# AS3364_bus_mixer_v2_0.net
KiCad netlist of a schematic drawn in EAGLE
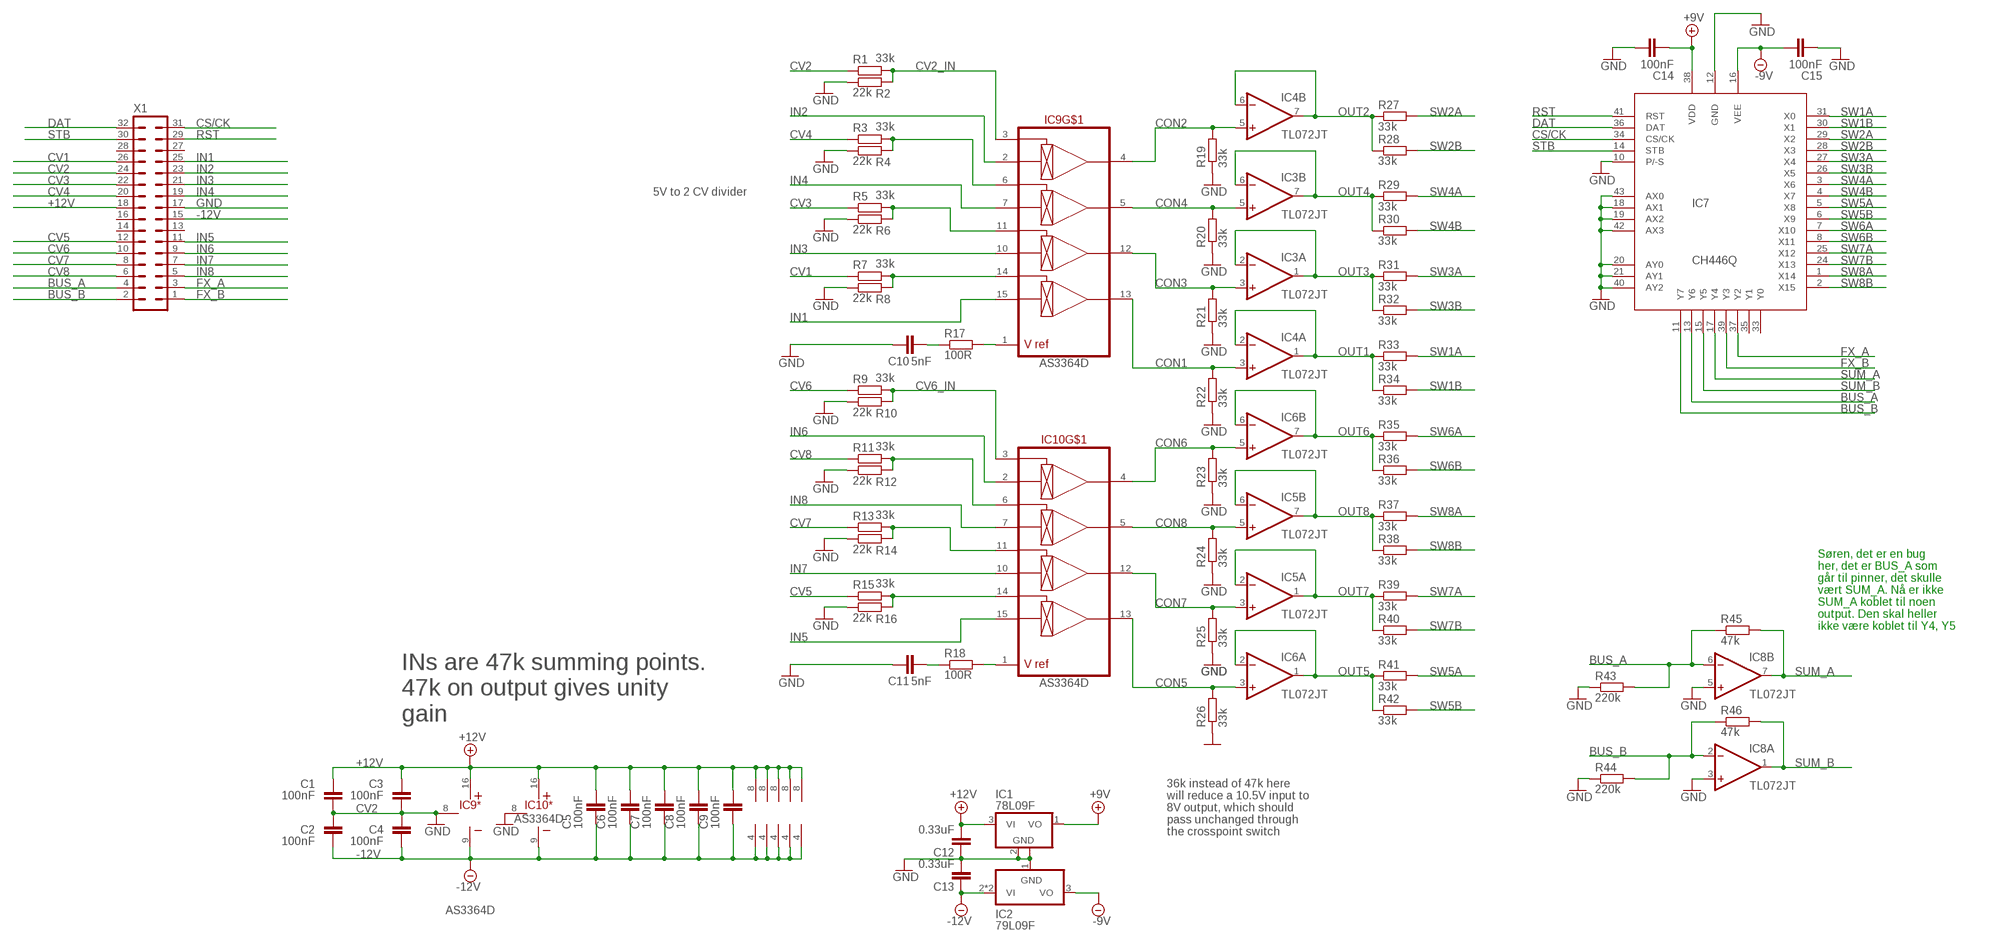
[diagram p0: schematic, sheet 1]

(export (version "E")
  (design (tool "Eeschema 10.0.6"))
  (components
    (comp (ref "C1")
      (value "100nF")
      (footprint "eagle-import:C0402")
      (libsource (lib "eagle-import") (part "C-EUC0402"))
    )
    (comp (ref "C2")
      (value "100nF")
      (footprint "eagle-import:C0402")
      (libsource (lib "eagle-import") (part "C-EUC0402"))
    )
    (comp (ref "C3")
      (value "100nF")
      (footprint "eagle-import:C0402")
      (libsource (lib "eagle-import") (part "C-EUC0402"))
    )
    (comp (ref "C4")
      (value "100nF")
      (footprint "eagle-import:C0402")
      (libsource (lib "eagle-import") (part "C-EUC0402"))
    )
    (comp (ref "C5")
      (value "100nF")
      (footprint "eagle-import:C0402")
      (libsource (lib "eagle-import") (part "C-EUC0402"))
    )
    (comp (ref "C6")
      (value "100nF")
      (footprint "eagle-import:C0402")
      (libsource (lib "eagle-import") (part "C-EUC0402"))
    )
    (comp (ref "C7")
      (value "100nF")
      (footprint "eagle-import:C0402")
      (libsource (lib "eagle-import") (part "C-EUC0402"))
    )
    (comp (ref "C8")
      (value "100nF")
      (footprint "eagle-import:C0402")
      (libsource (lib "eagle-import") (part "C-EUC0402"))
    )
    (comp (ref "C9")
      (value "100nF")
      (footprint "eagle-import:C0402")
      (libsource (lib "eagle-import") (part "C-EUC0402"))
    )
    (comp (ref "C10")
      (value "5nF")
      (footprint "eagle-import:C0402")
      (libsource (lib "eagle-import") (part "C-EUC0402"))
    )
    (comp (ref "C11")
      (value "5nF")
      (footprint "eagle-import:C0402")
      (libsource (lib "eagle-import") (part "C-EUC0402"))
    )
    (comp (ref "C12")
      (value "0.33uF")
      (footprint "eagle-import:C0603")
      (libsource (lib "eagle-import") (part "resistor_C-EUC0603"))
    )
    (comp (ref "C13")
      (value "0.33uF")
      (footprint "eagle-import:C0603")
      (libsource (lib "eagle-import") (part "resistor_C-EUC0603"))
    )
    (comp (ref "C14")
      (value "100nF")
      (footprint "eagle-import:C0402")
      (libsource (lib "eagle-import") (part "C-EUC0402"))
    )
    (comp (ref "C15")
      (value "100nF")
      (footprint "eagle-import:C0402")
      (libsource (lib "eagle-import") (part "C-EUC0402"))
    )
    (comp (ref "IC1")
      (value "78L09F")
      (footprint "eagle-import:SOT89")
      (libsource (lib "eagle-import") (part "78LF09"))
    )
    (comp (ref "IC2")
      (value "79L09F")
      (footprint "eagle-import:SOT89")
      (libsource (lib "eagle-import") (part "79LF09"))
    )
    (comp (ref "IC3")
      (value "TL072JT")
      (footprint "eagle-import:TSSOP8J")
      (libsource (lib "eagle-import") (part "TL072JT"))
    )
    (comp (ref "IC4")
      (value "TL072JT")
      (footprint "eagle-import:TSSOP8J")
      (libsource (lib "eagle-import") (part "TL072JT"))
    )
    (comp (ref "IC5")
      (value "TL072JT")
      (footprint "eagle-import:TSSOP8J")
      (libsource (lib "eagle-import") (part "TL072JT"))
    )
    (comp (ref "IC6")
      (value "TL072JT")
      (footprint "eagle-import:TSSOP8J")
      (libsource (lib "eagle-import") (part "TL072JT"))
    )
    (comp (ref "IC7")
      (value "CH446Q")
      (footprint "eagle-import:LQFP-44-J")
      (libsource (lib "eagle-import") (part "CH446Q"))
    )
    (comp (ref "IC8")
      (value "TL072JT")
      (footprint "eagle-import:TSSOP8J")
      (libsource (lib "eagle-import") (part "TL072JT"))
    )
    (comp (ref "IC9")
      (value "AS3364D")
      (footprint "eagle-import:DIL16J")
      (libsource (lib "eagle-import") (part "AS3364D"))
    )
    (comp (ref "IC10")
      (value "AS3364D")
      (footprint "eagle-import:DIL16J")
      (libsource (lib "eagle-import") (part "AS3364D"))
    )
    (comp (ref "R1")
      (value "33k")
      (footprint "eagle-import:R0402")
      (libsource (lib "eagle-import") (part "R-EU_R0402"))
    )
    (comp (ref "R2")
      (value "22k")
      (footprint "eagle-import:R0402")
      (libsource (lib "eagle-import") (part "R-EU_R0402"))
    )
    (comp (ref "R3")
      (value "33k")
      (footprint "eagle-import:R0402")
      (libsource (lib "eagle-import") (part "R-EU_R0402"))
    )
    (comp (ref "R4")
      (value "22k")
      (footprint "eagle-import:R0402")
      (libsource (lib "eagle-import") (part "R-EU_R0402"))
    )
    (comp (ref "R5")
      (value "33k")
      (footprint "eagle-import:R0402")
      (libsource (lib "eagle-import") (part "R-EU_R0402"))
    )
    (comp (ref "R6")
      (value "22k")
      (footprint "eagle-import:R0402")
      (libsource (lib "eagle-import") (part "R-EU_R0402"))
    )
    (comp (ref "R7")
      (value "33k")
      (footprint "eagle-import:R0402")
      (libsource (lib "eagle-import") (part "R-EU_R0402"))
    )
    (comp (ref "R8")
      (value "22k")
      (footprint "eagle-import:R0402")
      (libsource (lib "eagle-import") (part "R-EU_R0402"))
    )
    (comp (ref "R9")
      (value "33k")
      (footprint "eagle-import:R0402")
      (libsource (lib "eagle-import") (part "R-EU_R0402"))
    )
    (comp (ref "R10")
      (value "22k")
      (footprint "eagle-import:R0402")
      (libsource (lib "eagle-import") (part "R-EU_R0402"))
    )
    (comp (ref "R11")
      (value "33k")
      (footprint "eagle-import:R0402")
      (libsource (lib "eagle-import") (part "R-EU_R0402"))
    )
    (comp (ref "R12")
      (value "22k")
      (footprint "eagle-import:R0402")
      (libsource (lib "eagle-import") (part "R-EU_R0402"))
    )
    (comp (ref "R13")
      (value "33k")
      (footprint "eagle-import:R0402")
      (libsource (lib "eagle-import") (part "R-EU_R0402"))
    )
    (comp (ref "R14")
      (value "22k")
      (footprint "eagle-import:R0402")
      (libsource (lib "eagle-import") (part "R-EU_R0402"))
    )
    (comp (ref "R15")
      (value "33k")
      (footprint "eagle-import:R0402")
      (libsource (lib "eagle-import") (part "R-EU_R0402"))
    )
    (comp (ref "R16")
      (value "22k")
      (footprint "eagle-import:R0402")
      (libsource (lib "eagle-import") (part "R-EU_R0402"))
    )
    (comp (ref "R17")
      (value "100R")
      (footprint "eagle-import:R0402")
      (libsource (lib "eagle-import") (part "R-EU_R0402"))
    )
    (comp (ref "R18")
      (value "100R")
      (footprint "eagle-import:R0402")
      (libsource (lib "eagle-import") (part "R-EU_R0402"))
    )
    (comp (ref "R19")
      (value "33k")
      (footprint "eagle-import:R0402")
      (libsource (lib "eagle-import") (part "R-EU_R0402"))
    )
    (comp (ref "R20")
      (value "33k")
      (footprint "eagle-import:R0402")
      (libsource (lib "eagle-import") (part "R-EU_R0402"))
    )
    (comp (ref "R21")
      (value "33k")
      (footprint "eagle-import:R0402")
      (libsource (lib "eagle-import") (part "R-EU_R0402"))
    )
    (comp (ref "R22")
      (value "33k")
      (footprint "eagle-import:R0402")
      (libsource (lib "eagle-import") (part "R-EU_R0402"))
    )
    (comp (ref "R23")
      (value "33k")
      (footprint "eagle-import:R0402")
      (libsource (lib "eagle-import") (part "R-EU_R0402"))
    )
    (comp (ref "R24")
      (value "33k")
      (footprint "eagle-import:R0402")
      (libsource (lib "eagle-import") (part "R-EU_R0402"))
    )
    (comp (ref "R25")
      (value "33k")
      (footprint "eagle-import:R0402")
      (libsource (lib "eagle-import") (part "R-EU_R0402"))
    )
    (comp (ref "R26")
      (value "33k")
      (footprint "eagle-import:R0402")
      (libsource (lib "eagle-import") (part "R-EU_R0402"))
    )
    (comp (ref "R27")
      (value "33k")
      (footprint "eagle-import:R0402")
      (libsource (lib "eagle-import") (part "R-EU_R0402"))
    )
    (comp (ref "R28")
      (value "33k")
      (footprint "eagle-import:R0402")
      (libsource (lib "eagle-import") (part "R-EU_R0402"))
    )
    (comp (ref "R29")
      (value "33k")
      (footprint "eagle-import:R0402")
      (libsource (lib "eagle-import") (part "R-EU_R0402"))
    )
    (comp (ref "R30")
      (value "33k")
      (footprint "eagle-import:R0402")
      (libsource (lib "eagle-import") (part "R-EU_R0402"))
    )
    (comp (ref "R31")
      (value "33k")
      (footprint "eagle-import:R0402")
      (libsource (lib "eagle-import") (part "R-EU_R0402"))
    )
    (comp (ref "R32")
      (value "33k")
      (footprint "eagle-import:R0402")
      (libsource (lib "eagle-import") (part "R-EU_R0402"))
    )
    (comp (ref "R33")
      (value "33k")
      (footprint "eagle-import:R0402")
      (libsource (lib "eagle-import") (part "R-EU_R0402"))
    )
    (comp (ref "R34")
      (value "33k")
      (footprint "eagle-import:R0402")
      (libsource (lib "eagle-import") (part "R-EU_R0402"))
    )
    (comp (ref "R35")
      (value "33k")
      (footprint "eagle-import:R0402")
      (libsource (lib "eagle-import") (part "R-EU_R0402"))
    )
    (comp (ref "R36")
      (value "33k")
      (footprint "eagle-import:R0402")
      (libsource (lib "eagle-import") (part "R-EU_R0402"))
    )
    (comp (ref "R37")
      (value "33k")
      (footprint "eagle-import:R0402")
      (libsource (lib "eagle-import") (part "R-EU_R0402"))
    )
    (comp (ref "R38")
      (value "33k")
      (footprint "eagle-import:R0402")
      (libsource (lib "eagle-import") (part "R-EU_R0402"))
    )
    (comp (ref "R39")
      (value "33k")
      (footprint "eagle-import:R0402")
      (libsource (lib "eagle-import") (part "R-EU_R0402"))
    )
    (comp (ref "R40")
      (value "33k")
      (footprint "eagle-import:R0402")
      (libsource (lib "eagle-import") (part "R-EU_R0402"))
    )
    (comp (ref "R41")
      (value "33k")
      (footprint "eagle-import:R0402")
      (libsource (lib "eagle-import") (part "R-EU_R0402"))
    )
    (comp (ref "R42")
      (value "33k")
      (footprint "eagle-import:R0402")
      (libsource (lib "eagle-import") (part "R-EU_R0402"))
    )
    (comp (ref "R43")
      (value "220k")
      (footprint "eagle-import:R0402")
      (libsource (lib "eagle-import") (part "R-EU_R0402"))
    )
    (comp (ref "R44")
      (value "220k")
      (footprint "eagle-import:R0402")
      (libsource (lib "eagle-import") (part "R-EU_R0402"))
    )
    (comp (ref "R45")
      (value "47k")
      (footprint "eagle-import:R0402")
      (libsource (lib "eagle-import") (part "R-EU_R0402"))
    )
    (comp (ref "R46")
      (value "47k")
      (footprint "eagle-import:R0402")
      (libsource (lib "eagle-import") (part "R-EU_R0402"))
    )
    (comp (ref "X1")
      (value "MA16-2WJ")
      (footprint "eagle-import:MA16-2WJ")
      (libsource (lib "eagle-import") (part "MA16-2WJ"))
    )
  )
  (nets
    (net (code "1") (name "+9V") (class "Default")
      (node (ref "C14") (pin "1") (pinfunction "1_1") (pintype "passive"))
      (node (ref "IC1") (pin "1") (pinfunction "VO_1") (pintype "passive"))
      (node (ref "IC7") (pin "38") (pinfunction "VDD_38") (pintype "power_in"))
    )
    (net (code "2") (name "+12V") (class "Default")
      (node (ref "C1") (pin "2") (pinfunction "2_2") (pintype "passive"))
      (node (ref "C12") (pin "2") (pinfunction "2_2") (pintype "passive"))
      (node (ref "C3") (pin "2") (pinfunction "2_2") (pintype "passive"))
      (node (ref "C5") (pin "2") (pinfunction "2_2") (pintype "passive"))
      (node (ref "C6") (pin "2") (pinfunction "2_2") (pintype "passive"))
      (node (ref "C7") (pin "2") (pinfunction "2_2") (pintype "passive"))
      (node (ref "C8") (pin "2") (pinfunction "2_2") (pintype "passive"))
      (node (ref "C9") (pin "2") (pinfunction "2_2") (pintype "passive"))
      (node (ref "IC1") (pin "3") (pinfunction "VI_3") (pintype "input"))
      (node (ref "IC10") (pin "16") (pinfunction "V+_16") (pintype "power_in"))
      (node (ref "IC3") (pin "8") (pinfunction "V+_8") (pintype "power_in"))
      (node (ref "IC4") (pin "8") (pinfunction "V+_8") (pintype "power_in"))
      (node (ref "IC5") (pin "8") (pinfunction "V+_8") (pintype "power_in"))
      (node (ref "IC6") (pin "8") (pinfunction "V+_8") (pintype "power_in"))
      (node (ref "IC8") (pin "8") (pinfunction "V+_8") (pintype "power_in"))
      (node (ref "IC9") (pin "16") (pinfunction "V+_16") (pintype "power_in"))
      (node (ref "X1") (pin "18") (pinfunction "18_18") (pintype "passive"))
    )
    (net (code "3") (name "-9V") (class "Default")
      (node (ref "C15") (pin "2") (pinfunction "2_2") (pintype "passive"))
      (node (ref "IC2") (pin "3") (pinfunction "VO_3") (pintype "passive"))
      (node (ref "IC7") (pin "16") (pinfunction "VEE_16") (pintype "power_in"))
    )
    (net (code "4") (name "-12V") (class "Default")
      (node (ref "C13") (pin "1") (pinfunction "1_1") (pintype "passive"))
      (node (ref "C2") (pin "1") (pinfunction "1_1") (pintype "passive"))
      (node (ref "C4") (pin "1") (pinfunction "1_1") (pintype "passive"))
      (node (ref "C5") (pin "1") (pinfunction "1_1") (pintype "passive"))
      (node (ref "C6") (pin "1") (pinfunction "1_1") (pintype "passive"))
      (node (ref "C7") (pin "1") (pinfunction "1_1") (pintype "passive"))
      (node (ref "C8") (pin "1") (pinfunction "1_1") (pintype "passive"))
      (node (ref "C9") (pin "1") (pinfunction "1_1") (pintype "passive"))
      (node (ref "IC10") (pin "9") (pinfunction "V-_9") (pintype "power_in"))
      (node (ref "IC2") (pin "2") (pinfunction "VI_2") (pintype "input"))
      (node (ref "IC2") (pin "2@1") (pinfunction "VI_2@1") (pintype "input"))
      (node (ref "IC3") (pin "4") (pinfunction "V-_4") (pintype "power_in"))
      (node (ref "IC4") (pin "4") (pinfunction "V-_4") (pintype "power_in"))
      (node (ref "IC5") (pin "4") (pinfunction "V-_4") (pintype "power_in"))
      (node (ref "IC6") (pin "4") (pinfunction "V-_4") (pintype "power_in"))
      (node (ref "IC8") (pin "4") (pinfunction "V-_4") (pintype "power_in"))
      (node (ref "IC9") (pin "9") (pinfunction "V-_9") (pintype "power_in"))
      (node (ref "X1") (pin "15") (pinfunction "15_15") (pintype "passive"))
    )
    (net (code "5") (name "/BUS_A") (class "Default")
      (node (ref "IC7") (pin "13") (pinfunction "Y6_13") (pintype "bidirectional"))
      (node (ref "IC8") (pin "6") (pinfunction "-IN_6") (pintype "input"))
      (node (ref "R43") (pin "2") (pinfunction "2_2") (pintype "passive"))
      (node (ref "R45") (pin "1") (pinfunction "1_1") (pintype "passive"))
      (node (ref "X1") (pin "4") (pinfunction "4_4") (pintype "passive"))
    )
    (net (code "6") (name "/BUS_B") (class "Default")
      (node (ref "IC7") (pin "11") (pinfunction "Y7_11") (pintype "bidirectional"))
      (node (ref "IC8") (pin "2") (pinfunction "-IN_2") (pintype "input"))
      (node (ref "R44") (pin "2") (pinfunction "2_2") (pintype "passive"))
      (node (ref "R46") (pin "1") (pinfunction "1_1") (pintype "passive"))
      (node (ref "X1") (pin "2") (pinfunction "2_2") (pintype "passive"))
    )
    (net (code "7") (name "/CON1") (class "Default")
      (node (ref "IC4") (pin "3") (pinfunction "+IN_3") (pintype "input"))
      (node (ref "IC9") (pin "13") (pinfunction "OUT4_13") (pintype "output"))
      (node (ref "R22") (pin "2") (pinfunction "2_2") (pintype "passive"))
    )
    (net (code "8") (name "/CON2") (class "Default")
      (node (ref "IC4") (pin "5") (pinfunction "+IN_5") (pintype "input"))
      (node (ref "IC9") (pin "4") (pinfunction "OUT1_4") (pintype "output"))
      (node (ref "R19") (pin "2") (pinfunction "2_2") (pintype "passive"))
    )
    (net (code "9") (name "/CON3") (class "Default")
      (node (ref "IC3") (pin "3") (pinfunction "+IN_3") (pintype "input"))
      (node (ref "IC9") (pin "12") (pinfunction "OUT3_12") (pintype "output"))
      (node (ref "R21") (pin "2") (pinfunction "2_2") (pintype "passive"))
    )
    (net (code "10") (name "/CON4") (class "Default")
      (node (ref "IC3") (pin "5") (pinfunction "+IN_5") (pintype "input"))
      (node (ref "IC9") (pin "5") (pinfunction "OUT2_5") (pintype "output"))
      (node (ref "R20") (pin "2") (pinfunction "2_2") (pintype "passive"))
    )
    (net (code "11") (name "/CON5") (class "Default")
      (node (ref "IC10") (pin "13") (pinfunction "OUT4_13") (pintype "output"))
      (node (ref "IC6") (pin "3") (pinfunction "+IN_3") (pintype "input"))
      (node (ref "R26") (pin "2") (pinfunction "2_2") (pintype "passive"))
    )
    (net (code "12") (name "/CON6") (class "Default")
      (node (ref "IC10") (pin "4") (pinfunction "OUT1_4") (pintype "output"))
      (node (ref "IC6") (pin "5") (pinfunction "+IN_5") (pintype "input"))
      (node (ref "R23") (pin "2") (pinfunction "2_2") (pintype "passive"))
    )
    (net (code "13") (name "/CON7") (class "Default")
      (node (ref "IC10") (pin "12") (pinfunction "OUT3_12") (pintype "output"))
      (node (ref "IC5") (pin "3") (pinfunction "+IN_3") (pintype "input"))
      (node (ref "R25") (pin "2") (pinfunction "2_2") (pintype "passive"))
    )
    (net (code "14") (name "/CON8") (class "Default")
      (node (ref "IC10") (pin "5") (pinfunction "OUT2_5") (pintype "output"))
      (node (ref "IC5") (pin "5") (pinfunction "+IN_5") (pintype "input"))
      (node (ref "R24") (pin "2") (pinfunction "2_2") (pintype "passive"))
    )
    (net (code "15") (name "/CS{slash}CK") (class "Default")
      (node (ref "IC7") (pin "34") (pinfunction "CS/CK_34") (pintype "bidirectional"))
      (node (ref "X1") (pin "31") (pinfunction "31_31") (pintype "passive"))
    )
    (net (code "16") (name "/CV1") (class "Default")
      (node (ref "R7") (pin "1") (pinfunction "1_1") (pintype "passive"))
      (node (ref "X1") (pin "26") (pinfunction "26_26") (pintype "passive"))
    )
    (net (code "17") (name "/CV2") (class "Default")
      (node (ref "R1") (pin "1") (pinfunction "1_1") (pintype "passive"))
      (node (ref "X1") (pin "24") (pinfunction "24_24") (pintype "passive"))
    )
    (net (code "18") (name "/CV2_IN") (class "Default")
      (node (ref "IC9") (pin "3") (pinfunction "CV1_3") (pintype "input"))
      (node (ref "R1") (pin "2") (pinfunction "2_2") (pintype "passive"))
      (node (ref "R2") (pin "2") (pinfunction "2_2") (pintype "passive"))
    )
    (net (code "19") (name "/CV3") (class "Default")
      (node (ref "R5") (pin "1") (pinfunction "1_1") (pintype "passive"))
      (node (ref "X1") (pin "22") (pinfunction "22_22") (pintype "passive"))
    )
    (net (code "20") (name "/CV4") (class "Default")
      (node (ref "R3") (pin "1") (pinfunction "1_1") (pintype "passive"))
      (node (ref "X1") (pin "20") (pinfunction "20_20") (pintype "passive"))
    )
    (net (code "21") (name "/CV5") (class "Default")
      (node (ref "R15") (pin "1") (pinfunction "1_1") (pintype "passive"))
      (node (ref "X1") (pin "12") (pinfunction "12_12") (pintype "passive"))
    )
    (net (code "22") (name "/CV6") (class "Default")
      (node (ref "R9") (pin "1") (pinfunction "1_1") (pintype "passive"))
      (node (ref "X1") (pin "10") (pinfunction "10_10") (pintype "passive"))
    )
    (net (code "23") (name "/CV6_IN") (class "Default")
      (node (ref "IC10") (pin "3") (pinfunction "CV1_3") (pintype "input"))
      (node (ref "R10") (pin "2") (pinfunction "2_2") (pintype "passive"))
      (node (ref "R9") (pin "2") (pinfunction "2_2") (pintype "passive"))
    )
    (net (code "24") (name "/CV7") (class "Default")
      (node (ref "R13") (pin "1") (pinfunction "1_1") (pintype "passive"))
      (node (ref "X1") (pin "8") (pinfunction "8_8") (pintype "passive"))
    )
    (net (code "25") (name "/CV8") (class "Default")
      (node (ref "R11") (pin "1") (pinfunction "1_1") (pintype "passive"))
      (node (ref "X1") (pin "6") (pinfunction "6_6") (pintype "passive"))
    )
    (net (code "26") (name "/DAT") (class "Default")
      (node (ref "IC7") (pin "36") (pinfunction "DAT_36") (pintype "bidirectional"))
      (node (ref "X1") (pin "32") (pinfunction "32_32") (pintype "passive"))
    )
    (net (code "27") (name "/FX_A") (class "Default")
      (node (ref "IC7") (pin "37") (pinfunction "Y2_37") (pintype "bidirectional"))
      (node (ref "X1") (pin "3") (pinfunction "3_3") (pintype "passive"))
    )
    (net (code "28") (name "/FX_B") (class "Default")
      (node (ref "IC7") (pin "39") (pinfunction "Y3_39") (pintype "bidirectional"))
      (node (ref "X1") (pin "1") (pinfunction "1_1") (pintype "passive"))
    )
    (net (code "29") (name "/IN1") (class "Default")
      (node (ref "IC9") (pin "15") (pinfunction "IN4_15") (pintype "input"))
      (node (ref "X1") (pin "25") (pinfunction "25_25") (pintype "passive"))
    )
    (net (code "30") (name "/IN2") (class "Default")
      (node (ref "IC9") (pin "2") (pinfunction "IN1_2") (pintype "input"))
      (node (ref "X1") (pin "23") (pinfunction "23_23") (pintype "passive"))
    )
    (net (code "31") (name "/IN3") (class "Default")
      (node (ref "IC9") (pin "10") (pinfunction "IN3_10") (pintype "input"))
      (node (ref "X1") (pin "21") (pinfunction "21_21") (pintype "passive"))
    )
    (net (code "32") (name "/IN4") (class "Default")
      (node (ref "IC9") (pin "7") (pinfunction "IN2_7") (pintype "input"))
      (node (ref "X1") (pin "19") (pinfunction "19_19") (pintype "passive"))
    )
    (net (code "33") (name "/IN5") (class "Default")
      (node (ref "IC10") (pin "15") (pinfunction "IN4_15") (pintype "input"))
      (node (ref "X1") (pin "11") (pinfunction "11_11") (pintype "passive"))
    )
    (net (code "34") (name "/IN6") (class "Default")
      (node (ref "IC10") (pin "2") (pinfunction "IN1_2") (pintype "input"))
      (node (ref "X1") (pin "9") (pinfunction "9_9") (pintype "passive"))
    )
    (net (code "35") (name "/IN7") (class "Default")
      (node (ref "IC10") (pin "10") (pinfunction "IN3_10") (pintype "input"))
      (node (ref "X1") (pin "7") (pinfunction "7_7") (pintype "passive"))
    )
    (net (code "36") (name "/IN8") (class "Default")
      (node (ref "IC10") (pin "7") (pinfunction "IN2_7") (pintype "input"))
      (node (ref "X1") (pin "5") (pinfunction "5_5") (pintype "passive"))
    )
    (net (code "37") (name "/OUT1") (class "Default")
      (node (ref "IC4") (pin "1") (pinfunction "OUT_1") (pintype "output"))
      (node (ref "IC4") (pin "2") (pinfunction "-IN_2") (pintype "input"))
      (node (ref "R33") (pin "1") (pinfunction "1_1") (pintype "passive"))
      (node (ref "R34") (pin "1") (pinfunction "1_1") (pintype "passive"))
    )
    (net (code "38") (name "/OUT2") (class "Default")
      (node (ref "IC4") (pin "6") (pinfunction "-IN_6") (pintype "input"))
      (node (ref "IC4") (pin "7") (pinfunction "OUT_7") (pintype "output"))
      (node (ref "R27") (pin "1") (pinfunction "1_1") (pintype "passive"))
      (node (ref "R28") (pin "1") (pinfunction "1_1") (pintype "passive"))
    )
    (net (code "39") (name "/OUT3") (class "Default")
      (node (ref "IC3") (pin "1") (pinfunction "OUT_1") (pintype "output"))
      (node (ref "IC3") (pin "2") (pinfunction "-IN_2") (pintype "input"))
      (node (ref "R31") (pin "1") (pinfunction "1_1") (pintype "passive"))
      (node (ref "R32") (pin "1") (pinfunction "1_1") (pintype "passive"))
    )
    (net (code "40") (name "/OUT4") (class "Default")
      (node (ref "IC3") (pin "6") (pinfunction "-IN_6") (pintype "input"))
      (node (ref "IC3") (pin "7") (pinfunction "OUT_7") (pintype "output"))
      (node (ref "R29") (pin "1") (pinfunction "1_1") (pintype "passive"))
      (node (ref "R30") (pin "1") (pinfunction "1_1") (pintype "passive"))
    )
    (net (code "41") (name "/OUT5") (class "Default")
      (node (ref "IC6") (pin "1") (pinfunction "OUT_1") (pintype "output"))
      (node (ref "IC6") (pin "2") (pinfunction "-IN_2") (pintype "input"))
      (node (ref "R41") (pin "1") (pinfunction "1_1") (pintype "passive"))
      (node (ref "R42") (pin "1") (pinfunction "1_1") (pintype "passive"))
    )
    (net (code "42") (name "/OUT6") (class "Default")
      (node (ref "IC6") (pin "6") (pinfunction "-IN_6") (pintype "input"))
      (node (ref "IC6") (pin "7") (pinfunction "OUT_7") (pintype "output"))
      (node (ref "R35") (pin "1") (pinfunction "1_1") (pintype "passive"))
      (node (ref "R36") (pin "1") (pinfunction "1_1") (pintype "passive"))
    )
    (net (code "43") (name "/OUT7") (class "Default")
      (node (ref "IC5") (pin "1") (pinfunction "OUT_1") (pintype "output"))
      (node (ref "IC5") (pin "2") (pinfunction "-IN_2") (pintype "input"))
      (node (ref "R39") (pin "1") (pinfunction "1_1") (pintype "passive"))
      (node (ref "R40") (pin "1") (pinfunction "1_1") (pintype "passive"))
    )
    (net (code "44") (name "/OUT8") (class "Default")
      (node (ref "IC5") (pin "6") (pinfunction "-IN_6") (pintype "input"))
      (node (ref "IC5") (pin "7") (pinfunction "OUT_7") (pintype "output"))
      (node (ref "R37") (pin "1") (pinfunction "1_1") (pintype "passive"))
      (node (ref "R38") (pin "1") (pinfunction "1_1") (pintype "passive"))
    )
    (net (code "45") (name "/RST") (class "Default")
      (node (ref "IC7") (pin "41") (pinfunction "RST_41") (pintype "bidirectional"))
      (node (ref "X1") (pin "29") (pinfunction "29_29") (pintype "passive"))
    )
    (net (code "46") (name "/STB") (class "Default")
      (node (ref "IC7") (pin "14") (pinfunction "STB_14") (pintype "bidirectional"))
      (node (ref "X1") (pin "30") (pinfunction "30_30") (pintype "passive"))
    )
    (net (code "47") (name "/SUM_A") (class "Default")
      (node (ref "IC7") (pin "17") (pinfunction "Y4_17") (pintype "bidirectional"))
      (node (ref "IC8") (pin "7") (pinfunction "OUT_7") (pintype "output"))
      (node (ref "R45") (pin "2") (pinfunction "2_2") (pintype "passive"))
    )
    (net (code "48") (name "/SUM_B") (class "Default")
      (node (ref "IC7") (pin "15") (pinfunction "Y5_15") (pintype "bidirectional"))
      (node (ref "IC8") (pin "1") (pinfunction "OUT_1") (pintype "output"))
      (node (ref "R46") (pin "2") (pinfunction "2_2") (pintype "passive"))
    )
    (net (code "49") (name "/SW1A") (class "Default")
      (node (ref "IC7") (pin "31") (pinfunction "X0_31") (pintype "bidirectional"))
      (node (ref "R33") (pin "2") (pinfunction "2_2") (pintype "passive"))
    )
    (net (code "50") (name "/SW1B") (class "Default")
      (node (ref "IC7") (pin "30") (pinfunction "X1_30") (pintype "bidirectional"))
      (node (ref "R34") (pin "2") (pinfunction "2_2") (pintype "passive"))
    )
    (net (code "51") (name "/SW2A") (class "Default")
      (node (ref "IC7") (pin "29") (pinfunction "X2_29") (pintype "bidirectional"))
      (node (ref "R27") (pin "2") (pinfunction "2_2") (pintype "passive"))
    )
    (net (code "52") (name "/SW2B") (class "Default")
      (node (ref "IC7") (pin "28") (pinfunction "X3_28") (pintype "bidirectional"))
      (node (ref "R28") (pin "2") (pinfunction "2_2") (pintype "passive"))
    )
    (net (code "53") (name "/SW3A") (class "Default")
      (node (ref "IC7") (pin "27") (pinfunction "X4_27") (pintype "bidirectional"))
      (node (ref "R31") (pin "2") (pinfunction "2_2") (pintype "passive"))
    )
    (net (code "54") (name "/SW3B") (class "Default")
      (node (ref "IC7") (pin "26") (pinfunction "X5_26") (pintype "bidirectional"))
      (node (ref "R32") (pin "2") (pinfunction "2_2") (pintype "passive"))
    )
    (net (code "55") (name "/SW4A") (class "Default")
      (node (ref "IC7") (pin "3") (pinfunction "X6_3") (pintype "bidirectional"))
      (node (ref "R29") (pin "2") (pinfunction "2_2") (pintype "passive"))
    )
    (net (code "56") (name "/SW4B") (class "Default")
      (node (ref "IC7") (pin "4") (pinfunction "X7_4") (pintype "bidirectional"))
      (node (ref "R30") (pin "2") (pinfunction "2_2") (pintype "passive"))
    )
    (net (code "57") (name "/SW5A") (class "Default")
      (node (ref "IC7") (pin "5") (pinfunction "X8_5") (pintype "bidirectional"))
      (node (ref "R41") (pin "2") (pinfunction "2_2") (pintype "passive"))
    )
    (net (code "58") (name "/SW5B") (class "Default")
      (node (ref "IC7") (pin "6") (pinfunction "X9_6") (pintype "bidirectional"))
      (node (ref "R42") (pin "2") (pinfunction "2_2") (pintype "passive"))
    )
    (net (code "59") (name "/SW6A") (class "Default")
      (node (ref "IC7") (pin "7") (pinfunction "X10_7") (pintype "bidirectional"))
      (node (ref "R35") (pin "2") (pinfunction "2_2") (pintype "passive"))
    )
    (net (code "60") (name "/SW6B") (class "Default")
      (node (ref "IC7") (pin "8") (pinfunction "X11_8") (pintype "bidirectional"))
      (node (ref "R36") (pin "2") (pinfunction "2_2") (pintype "passive"))
    )
    (net (code "61") (name "/SW7A") (class "Default")
      (node (ref "IC7") (pin "25") (pinfunction "X12_25") (pintype "bidirectional"))
      (node (ref "R39") (pin "2") (pinfunction "2_2") (pintype "passive"))
    )
    (net (code "62") (name "/SW7B") (class "Default")
      (node (ref "IC7") (pin "24") (pinfunction "X13_24") (pintype "bidirectional"))
      (node (ref "R40") (pin "2") (pinfunction "2_2") (pintype "passive"))
    )
    (net (code "63") (name "/SW8A") (class "Default")
      (node (ref "IC7") (pin "1") (pinfunction "X14_1") (pintype "bidirectional"))
      (node (ref "R37") (pin "2") (pinfunction "2_2") (pintype "passive"))
    )
    (net (code "64") (name "/SW8B") (class "Default")
      (node (ref "IC7") (pin "2") (pinfunction "X15_2") (pintype "bidirectional"))
      (node (ref "R38") (pin "2") (pinfunction "2_2") (pintype "passive"))
    )
    (net (code "65") (name "GND") (class "Default")
      (node (ref "C1") (pin "1") (pinfunction "1_1") (pintype "passive"))
      (node (ref "C10") (pin "1") (pinfunction "1_1") (pintype "passive"))
      (node (ref "C11") (pin "1") (pinfunction "1_1") (pintype "passive"))
      (node (ref "C12") (pin "1") (pinfunction "1_1") (pintype "passive"))
      (node (ref "C13") (pin "2") (pinfunction "2_2") (pintype "passive"))
      (node (ref "C14") (pin "2") (pinfunction "2_2") (pintype "passive"))
      (node (ref "C15") (pin "1") (pinfunction "1_1") (pintype "passive"))
      (node (ref "C2") (pin "2") (pinfunction "2_2") (pintype "passive"))
      (node (ref "C3") (pin "1") (pinfunction "1_1") (pintype "passive"))
      (node (ref "C4") (pin "2") (pinfunction "2_2") (pintype "passive"))
      (node (ref "IC1") (pin "2") (pinfunction "GND_2") (pintype "passive"))
      (node (ref "IC1") (pin "2@1") (pinfunction "GND_2@1") (pintype "passive"))
      (node (ref "IC10") (pin "8") (pinfunction "GND_8") (pintype "power_in"))
      (node (ref "IC2") (pin "1") (pinfunction "GND_1") (pintype "passive"))
      (node (ref "IC7") (pin "10") (pinfunction "P/-S_10") (pintype "bidirectional"))
      (node (ref "IC7") (pin "12") (pinfunction "GND_12") (pintype "power_in"))
      (node (ref "IC7") (pin "18") (pinfunction "AX1_18") (pintype "bidirectional"))
      (node (ref "IC7") (pin "19") (pinfunction "AX2_19") (pintype "bidirectional"))
      (node (ref "IC7") (pin "20") (pinfunction "AY0_20") (pintype "bidirectional"))
      (node (ref "IC7") (pin "21") (pinfunction "AY1_21") (pintype "bidirectional"))
      (node (ref "IC7") (pin "40") (pinfunction "AY2_40") (pintype "bidirectional"))
      (node (ref "IC7") (pin "42") (pinfunction "AX3_42") (pintype "bidirectional"))
      (node (ref "IC7") (pin "43") (pinfunction "AX0_43") (pintype "bidirectional"))
      (node (ref "IC8") (pin "3") (pinfunction "+IN_3") (pintype "input"))
      (node (ref "IC8") (pin "5") (pinfunction "+IN_5") (pintype "input"))
      (node (ref "IC9") (pin "8") (pinfunction "GND_8") (pintype "power_in"))
      (node (ref "R10") (pin "1") (pinfunction "1_1") (pintype "passive"))
      (node (ref "R12") (pin "1") (pinfunction "1_1") (pintype "passive"))
      (node (ref "R14") (pin "1") (pinfunction "1_1") (pintype "passive"))
      (node (ref "R16") (pin "1") (pinfunction "1_1") (pintype "passive"))
      (node (ref "R19") (pin "1") (pinfunction "1_1") (pintype "passive"))
      (node (ref "R2") (pin "1") (pinfunction "1_1") (pintype "passive"))
      (node (ref "R20") (pin "1") (pinfunction "1_1") (pintype "passive"))
      (node (ref "R21") (pin "1") (pinfunction "1_1") (pintype "passive"))
      (node (ref "R22") (pin "1") (pinfunction "1_1") (pintype "passive"))
      (node (ref "R23") (pin "1") (pinfunction "1_1") (pintype "passive"))
      (node (ref "R24") (pin "1") (pinfunction "1_1") (pintype "passive"))
      (node (ref "R25") (pin "1") (pinfunction "1_1") (pintype "passive"))
      (node (ref "R26") (pin "1") (pinfunction "1_1") (pintype "passive"))
      (node (ref "R4") (pin "1") (pinfunction "1_1") (pintype "passive"))
      (node (ref "R43") (pin "1") (pinfunction "1_1") (pintype "passive"))
      (node (ref "R44") (pin "1") (pinfunction "1_1") (pintype "passive"))
      (node (ref "R6") (pin "1") (pinfunction "1_1") (pintype "passive"))
      (node (ref "R8") (pin "1") (pinfunction "1_1") (pintype "passive"))
      (node (ref "X1") (pin "17") (pinfunction "17_17") (pintype "passive"))
    )
    (net (code "66") (name "Net-(C10-Pad2)") (class "Default")
      (node (ref "C10") (pin "2") (pinfunction "2_2") (pintype "passive"))
      (node (ref "R17") (pin "1") (pinfunction "1_1") (pintype "passive"))
    )
    (net (code "67") (name "Net-(C11-Pad2)") (class "Default")
      (node (ref "C11") (pin "2") (pinfunction "2_2") (pintype "passive"))
      (node (ref "R18") (pin "1") (pinfunction "1_1") (pintype "passive"))
    )
    (net (code "68") (name "Net-(IC9B-CV2)") (class "Default")
      (node (ref "IC9") (pin "6") (pinfunction "CV2_6") (pintype "input"))
      (node (ref "R3") (pin "2") (pinfunction "2_2") (pintype "passive"))
      (node (ref "R4") (pin "2") (pinfunction "2_2") (pintype "passive"))
    )
    (net (code "69") (name "Net-(IC9B-CV3)") (class "Default")
      (node (ref "IC9") (pin "11") (pinfunction "CV3_11") (pintype "input"))
      (node (ref "R5") (pin "2") (pinfunction "2_2") (pintype "passive"))
      (node (ref "R6") (pin "2") (pinfunction "2_2") (pintype "passive"))
    )
    (net (code "70") (name "Net-(IC9B-CV4)") (class "Default")
      (node (ref "IC9") (pin "14") (pinfunction "CV4_14") (pintype "input"))
      (node (ref "R7") (pin "2") (pinfunction "2_2") (pintype "passive"))
      (node (ref "R8") (pin "2") (pinfunction "2_2") (pintype "passive"))
    )
    (net (code "71") (name "Net-(IC9B-VREF)") (class "Default")
      (node (ref "IC9") (pin "1") (pinfunction "VREF_1") (pintype "output"))
      (node (ref "R17") (pin "2") (pinfunction "2_2") (pintype "passive"))
    )
    (net (code "72") (name "Net-(IC10B-CV2)") (class "Default")
      (node (ref "IC10") (pin "6") (pinfunction "CV2_6") (pintype "input"))
      (node (ref "R11") (pin "2") (pinfunction "2_2") (pintype "passive"))
      (node (ref "R12") (pin "2") (pinfunction "2_2") (pintype "passive"))
    )
    (net (code "73") (name "Net-(IC10B-CV3)") (class "Default")
      (node (ref "IC10") (pin "11") (pinfunction "CV3_11") (pintype "input"))
      (node (ref "R13") (pin "2") (pinfunction "2_2") (pintype "passive"))
      (node (ref "R14") (pin "2") (pinfunction "2_2") (pintype "passive"))
    )
    (net (code "74") (name "Net-(IC10B-CV4)") (class "Default")
      (node (ref "IC10") (pin "14") (pinfunction "CV4_14") (pintype "input"))
      (node (ref "R15") (pin "2") (pinfunction "2_2") (pintype "passive"))
      (node (ref "R16") (pin "2") (pinfunction "2_2") (pintype "passive"))
    )
    (net (code "75") (name "Net-(IC10B-VREF)") (class "Default")
      (node (ref "IC10") (pin "1") (pinfunction "VREF_1") (pintype "output"))
      (node (ref "R18") (pin "2") (pinfunction "2_2") (pintype "passive"))
    )
    (net (code "76") (name "unconnected-(IC7-Y0-Pad33)") (class "Default")
      (node (ref "IC7") (pin "33") (pinfunction "Y0_33") (pintype "bidirectional"))
    )
    (net (code "77") (name "unconnected-(IC7-Y1-Pad35)") (class "Default")
      (node (ref "IC7") (pin "35") (pinfunction "Y1_35") (pintype "bidirectional"))
    )
    (net (code "78") (name "unconnected-(X1-Pad13)") (class "Default")
      (node (ref "X1") (pin "13") (pinfunction "13_13") (pintype "passive"))
    )
    (net (code "79") (name "unconnected-(X1-Pad14)") (class "Default")
      (node (ref "X1") (pin "14") (pinfunction "14_14") (pintype "passive"))
    )
    (net (code "80") (name "unconnected-(X1-Pad16)") (class "Default")
      (node (ref "X1") (pin "16") (pinfunction "16_16") (pintype "passive"))
    )
    (net (code "81") (name "unconnected-(X1-Pad27)") (class "Default")
      (node (ref "X1") (pin "27") (pinfunction "27_27") (pintype "passive"))
    )
    (net (code "82") (name "unconnected-(X1-Pad28)") (class "Default")
      (node (ref "X1") (pin "28") (pinfunction "28_28") (pintype "passive"))
    )
  )
)
